# JD-ESPFSH-V1.net
KiCad netlist of a schematic drawn in Altium Designer
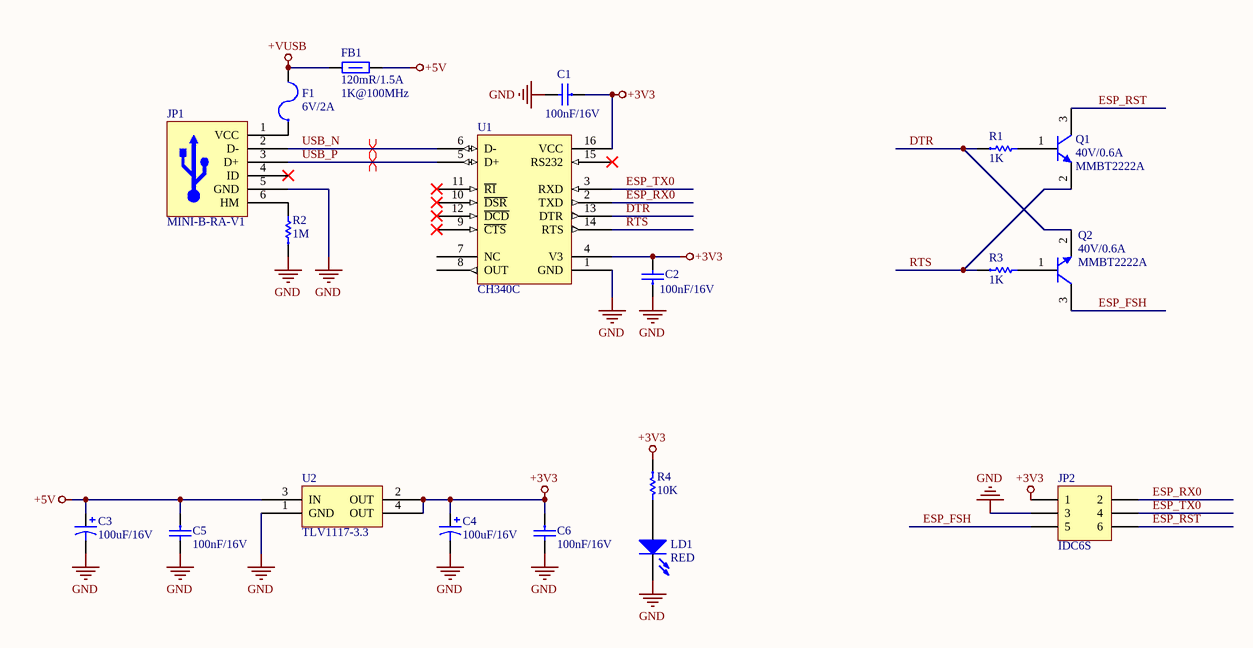
[diagram p0: JD-ESPFSH-V1.SchDoc]

(export (version "E")
  (design (tool "Eeschema 10.0.6"))
  (components
    (comp (ref "C1")
      (value "100nF/16V")
      (footprint "CAP-CER0603-0.8H")
      (description "CAP CER 100nF/16V 10% X7R 0603 SMD")
      (fields (field (name "MFR") "YAGEO"))
      (libsource (lib "ADLibEP") (part "CAPCER0008 0603 100nF/16V"))
    )
    (comp (ref "C2")
      (value "100nF/16V")
      (footprint "CAP-CER0603-0.8H")
      (description "CAP CER 100nF/16V 10% X7R 0603 SMD")
      (fields (field (name "MFR") "YAGEO"))
      (libsource (lib "ADLibEP") (part "CAPCER0008 0603 100nF/16V"))
    )
    (comp (ref "C3")
      (value "100uF/16V")
      (footprint "CAP-ALU-6.3D5.8H-SMD")
      (description "CAP ALU 100uF/16V 20% 2K105 2.2P 6.3X5.8 SMD")
      (fields (field (name "MFR") "NICHICON"))
      (libsource (lib "ADLibEP") (part "CAPALU0012 6.3X5.8 100uF/16V SMD"))
    )
    (comp (ref "C4")
      (value "100uF/16V")
      (footprint "CAP-ALU-6.3D5.8H-SMD")
      (description "CAP ALU 100uF/16V 20% 2K105 2.2P 6.3X5.8 SMD")
      (fields (field (name "MFR") "NICHICON"))
      (libsource (lib "ADLibEP") (part "CAPALU0012 6.3X5.8 100uF/16V SMD"))
    )
    (comp (ref "C5")
      (value "100nF/16V")
      (footprint "CAP-CER0603-0.8H")
      (description "CAP CER 100nF/16V 10% X7R 0603 SMD")
      (fields (field (name "MFR") "YAGEO"))
      (libsource (lib "ADLibEP") (part "CAPCER0008 0603 100nF/16V"))
    )
    (comp (ref "C6")
      (value "100nF/16V")
      (footprint "CAP-CER0603-0.8H")
      (description "CAP CER 100nF/16V 10% X7R 0603 SMD")
      (fields (field (name "MFR") "YAGEO"))
      (libsource (lib "ADLibEP") (part "CAPCER0008 0603 100nF/16V"))
    )
    (comp (ref "F1")
      (value "6V/2A")
      (footprint "FUS-PTC-SMD1206-1.6H")
      (description "FUS PTC RST 6V 2A 1206 SMD")
      (fields (field (name "MFR") "BOURNS"))
      (libsource (lib "ADLibEP") (part "FUSPTC0001 1206 6V/2A"))
    )
    (comp (ref "FB1")
      (value "120mR/1.5A")
      (footprint "IND-C0805-1.1H")
      (description "FIL FER CHP 1LN 120mR 25% 1.5A 1K@100MHz 0805 SMD")
      (fields (field (name "NOTE") "1K@100MHz") (field (name "MFR") "SUNLORD"))
      (libsource (lib "ADLibEP") (part "FILFER0003 0805 120mR/1.5A"))
    )
    (comp (ref "JP1")
      (value "MINI-B-RA-V1")
      (footprint "CON-USB-MINI-B-RA-V1-SMD")
      (description "CON USB RCPT MINI-B 5POS RA V1 SMD")
      (fields (field (name "MFR") "HANBO"))
      (libsource (lib "ADLibEP") (part "CONUSB0001 MINI-B-RA-V1"))
    )
    (comp (ref "JP2")
      (value "IDC6S")
      (footprint "CON-IDC6-2.54P9.3H-S-THR")
      (description "CON W2B IDC2.54M-2X3V-9H THR")
      (fields (field (name "MFR") "XFCN"))
      (libsource (lib "ADLibEP") (part "CONW2B0010 IDC2.54M-6PV"))
    )
    (comp (ref "LD1")
      (value "RED")
      (footprint "LED-IND0603-RED-0.6H")
      (description "LED IND RED CLR 2V 20mA 0603 SMD")
      (fields (field (name "MFR") "WURTH"))
      (libsource (lib "ADLibEP") (part "LEDIND0001 0603 RED"))
    )
    (comp (ref "Q1")
      (value "40V/0.6A")
      (footprint "SOT23-3-1.1H")
      (description "BJT NPN 40V 0.6A SOT23-3 SMD")
      (fields (field (name "NOTE") "MMBT2222A") (field (name "MFR") "ONSEMI"))
      (libsource (lib "ADLibEP") (part "BJTNPN0001 SOT23 40V/0.6A"))
    )
    (comp (ref "Q2")
      (value "40V/0.6A")
      (footprint "SOT23-3-1.1H")
      (description "BJT NPN 40V 0.6A SOT23-3 SMD")
      (fields (field (name "NOTE") "MMBT2222A") (field (name "MFR") "ONSEMI"))
      (libsource (lib "ADLibEP") (part "BJTNPN0001 SOT23 40V/0.6A"))
    )
    (comp (ref "R1")
      (value "1K")
      (footprint "RES-CHP0603-0.6H")
      (description "RES CHP 1K 1% 1/10W 0603 SMD")
      (fields (field (name "MFR") "YAGEO"))
      (libsource (lib "ADLibEP") (part "RESCHP0007 0603 1% 1K"))
    )
    (comp (ref "R2")
      (value "1M")
      (footprint "RES-CHP0603-0.6H")
      (description "RES CHP 1M 1% 1/10W 0603 SMD")
      (fields (field (name "MFR") "YAGEO"))
      (libsource (lib "ADLibEP") (part "RESCHP0036 0603 1% 1M"))
    )
    (comp (ref "R3")
      (value "1K")
      (footprint "RES-CHP0603-0.6H")
      (description "RES CHP 1K 1% 1/10W 0603 SMD")
      (fields (field (name "MFR") "YAGEO"))
      (libsource (lib "ADLibEP") (part "RESCHP0007 0603 1% 1K"))
    )
    (comp (ref "R4")
      (value "10K")
      (footprint "RES-CHP0603-0.6H")
      (description "RES CHP 10K 1% 1/10W 0603 SMD")
      (fields (field (name "MFR") "YAGEO"))
      (libsource (lib "ADLibEP") (part "RESCHP0008 0603 1% 10K"))
    )
    (comp (ref "U1")
      (value "CH340C")
      (footprint "SOIC-16M-1.75H")
      (description "ICS INT USB2UART CH340C 16SOIC SMD")
      (fields (field (name "MFR") "WCH"))
      (libsource (lib "ADLibEP") (part "ICSINT0008 CH340C"))
    )
    (comp (ref "U2")
      (value "TLV1117-3.3")
      (footprint "SOT223-4N-1.8H")
      (description "ICS VRE TLV1117-33 3V3 0.8A SOT223 SMD")
      (fields (field (name "MFR") "TI"))
      (libsource (lib "ADLibEP") (part "ICSVRE0001 SOT223 TLV1117-3.3"))
    )
  )
  (nets
    (net (code "1") (name "+3V3") (class "Default")
      (node (ref "C1") (pin "1") (pinfunction "1_1") (pintype "passive"))
      (node (ref "C2") (pin "2") (pinfunction "2_2") (pintype "passive"))
      (node (ref "C4") (pin "1") (pinfunction "1_1") (pintype "passive"))
      (node (ref "C6") (pin "1") (pinfunction "1_1") (pintype "passive"))
      (node (ref "JP2") (pin "1") (pinfunction "1_1") (pintype "passive"))
      (node (ref "R4") (pin "1") (pinfunction "1_1") (pintype "passive"))
      (node (ref "U1") (pin "16") (pinfunction "VCC_16") (pintype "power_in"))
      (node (ref "U1") (pin "4") (pinfunction "V3_4") (pintype "power_in"))
      (node (ref "U2") (pin "2") (pinfunction "OUT_2") (pintype "passive"))
      (node (ref "U2") (pin "4") (pinfunction "OUT_4") (pintype "passive"))
    )
    (net (code "2") (name "+5V") (class "Default")
      (node (ref "C3") (pin "1") (pinfunction "1_1") (pintype "passive"))
      (node (ref "C5") (pin "1") (pinfunction "1_1") (pintype "passive"))
      (node (ref "FB1") (pin "2") (pinfunction "2_2") (pintype "passive"))
      (node (ref "U2") (pin "3") (pinfunction "IN_3") (pintype "passive"))
    )
    (net (code "3") (name "+VUSB") (class "Default")
      (node (ref "F1") (pin "2") (pinfunction "2_2") (pintype "passive"))
      (node (ref "FB1") (pin "1") (pinfunction "1_1") (pintype "passive"))
    )
    (net (code "4") (name "/DTR") (class "Default")
      (node (ref "Q2") (pin "2") (pinfunction "E_2") (pintype "passive"))
      (node (ref "R1") (pin "1") (pinfunction "1_1") (pintype "passive"))
      (node (ref "U1") (pin "13") (pinfunction "DTR_13") (pintype "output"))
    )
    (net (code "5") (name "/ESP_FSH") (class "Default")
      (node (ref "JP2") (pin "5") (pinfunction "5_5") (pintype "passive"))
      (node (ref "Q2") (pin "3") (pinfunction "C_3") (pintype "passive"))
    )
    (net (code "6") (name "/ESP_RST") (class "Default")
      (node (ref "JP2") (pin "6") (pinfunction "6_6") (pintype "passive"))
      (node (ref "Q1") (pin "3") (pinfunction "C_3") (pintype "passive"))
    )
    (net (code "7") (name "/ESP_RX0") (class "Default")
      (node (ref "JP2") (pin "2") (pinfunction "2_2") (pintype "passive"))
      (node (ref "U1") (pin "2") (pinfunction "TXD_2") (pintype "output"))
    )
    (net (code "8") (name "/ESP_TX0") (class "Default")
      (node (ref "JP2") (pin "4") (pinfunction "4_4") (pintype "passive"))
      (node (ref "U1") (pin "3") (pinfunction "RXD_3") (pintype "input"))
    )
    (net (code "9") (name "/RTS") (class "Default")
      (node (ref "Q1") (pin "2") (pinfunction "E_2") (pintype "passive"))
      (node (ref "R3") (pin "1") (pinfunction "1_1") (pintype "passive"))
      (node (ref "U1") (pin "14") (pinfunction "RTS_14") (pintype "output"))
    )
    (net (code "10") (name "/USB_N") (class "Default")
      (node (ref "JP1") (pin "2") (pinfunction "D-_2") (pintype "passive"))
      (node (ref "U1") (pin "6") (pinfunction "D-_6") (pintype "bidirectional"))
    )
    (net (code "11") (name "/USB_P") (class "Default")
      (node (ref "JP1") (pin "3") (pinfunction "D+_3") (pintype "passive"))
      (node (ref "U1") (pin "5") (pinfunction "D+_5") (pintype "bidirectional"))
    )
    (net (code "12") (name "GND") (class "Default")
      (node (ref "C1") (pin "2") (pinfunction "2_2") (pintype "passive"))
      (node (ref "C2") (pin "1") (pinfunction "1_1") (pintype "passive"))
      (node (ref "C3") (pin "2") (pinfunction "2_2") (pintype "passive"))
      (node (ref "C4") (pin "2") (pinfunction "2_2") (pintype "passive"))
      (node (ref "C5") (pin "2") (pinfunction "2_2") (pintype "passive"))
      (node (ref "C6") (pin "2") (pinfunction "2_2") (pintype "passive"))
      (node (ref "JP1") (pin "5") (pinfunction "GND_5") (pintype "passive"))
      (node (ref "JP2") (pin "3") (pinfunction "3_3") (pintype "passive"))
      (node (ref "LD1") (pin "2") (pinfunction "K_2") (pintype "passive"))
      (node (ref "R2") (pin "1") (pinfunction "1_1") (pintype "passive"))
      (node (ref "U1") (pin "1") (pinfunction "GND_1") (pintype "power_in"))
      (node (ref "U2") (pin "1") (pinfunction "GND_1") (pintype "passive"))
    )
    (net (code "13") (name "Net-(JP1-HM)") (class "Default")
      (node (ref "JP1") (pin "6") (pinfunction "HM_6") (pintype "passive"))
      (node (ref "R2") (pin "2") (pinfunction "2_2") (pintype "passive"))
    )
    (net (code "14") (name "Net-(JP1-VCC)") (class "Default")
      (node (ref "F1") (pin "1") (pinfunction "1_1") (pintype "passive"))
      (node (ref "JP1") (pin "1") (pinfunction "VCC_1") (pintype "passive"))
    )
    (net (code "15") (name "Net-(LD1-A)") (class "Default")
      (node (ref "LD1") (pin "1") (pinfunction "A_1") (pintype "passive"))
      (node (ref "R4") (pin "2") (pinfunction "2_2") (pintype "passive"))
    )
    (net (code "16") (name "Net-(Q1-B)") (class "Default")
      (node (ref "Q1") (pin "1") (pinfunction "B_1") (pintype "passive"))
      (node (ref "R1") (pin "2") (pinfunction "2_2") (pintype "passive"))
    )
    (net (code "17") (name "Net-(Q2-B)") (class "Default")
      (node (ref "Q2") (pin "1") (pinfunction "B_1") (pintype "passive"))
      (node (ref "R3") (pin "2") (pinfunction "2_2") (pintype "passive"))
    )
    (net (code "18") (name "unconnected-(JP1-ID-Pad4)") (class "Default")
      (node (ref "JP1") (pin "4") (pinfunction "ID_4") (pintype "passive+no_connect"))
    )
    (net (code "19") (name "unconnected-(U1-NC-Pad7)") (class "Default")
      (node (ref "U1") (pin "7") (pinfunction "NC_7") (pintype "passive"))
    )
    (net (code "20") (name "unconnected-(U1-OUT-Pad8)") (class "Default")
      (node (ref "U1") (pin "8") (pinfunction "OUT_8") (pintype "output"))
    )
    (net (code "21") (name "unconnected-(U1-RS232-Pad15)") (class "Default")
      (node (ref "U1") (pin "15") (pinfunction "RS232_15") (pintype "input+no_connect"))
    )
    (net (code "22") (name "unconnected-(U1-~{CTS}-Pad9)") (class "Default")
      (node (ref "U1") (pin "9") (pinfunction "~{CTS}_9") (pintype "input+no_connect"))
    )
    (net (code "23") (name "unconnected-(U1-~{DCD}-Pad12)") (class "Default")
      (node (ref "U1") (pin "12") (pinfunction "~{DCD}_12") (pintype "input+no_connect"))
    )
    (net (code "24") (name "unconnected-(U1-~{DSR}-Pad10)") (class "Default")
      (node (ref "U1") (pin "10") (pinfunction "~{DSR}_10") (pintype "input+no_connect"))
    )
    (net (code "25") (name "unconnected-(U1-~{RI}-Pad11)") (class "Default")
      (node (ref "U1") (pin "11") (pinfunction "~{RI}_11") (pintype "input+no_connect"))
    )
  )
)
